# item_2022_BlockDiagram_01.net
KiCad netlist of a schematic drawn in EAGLE
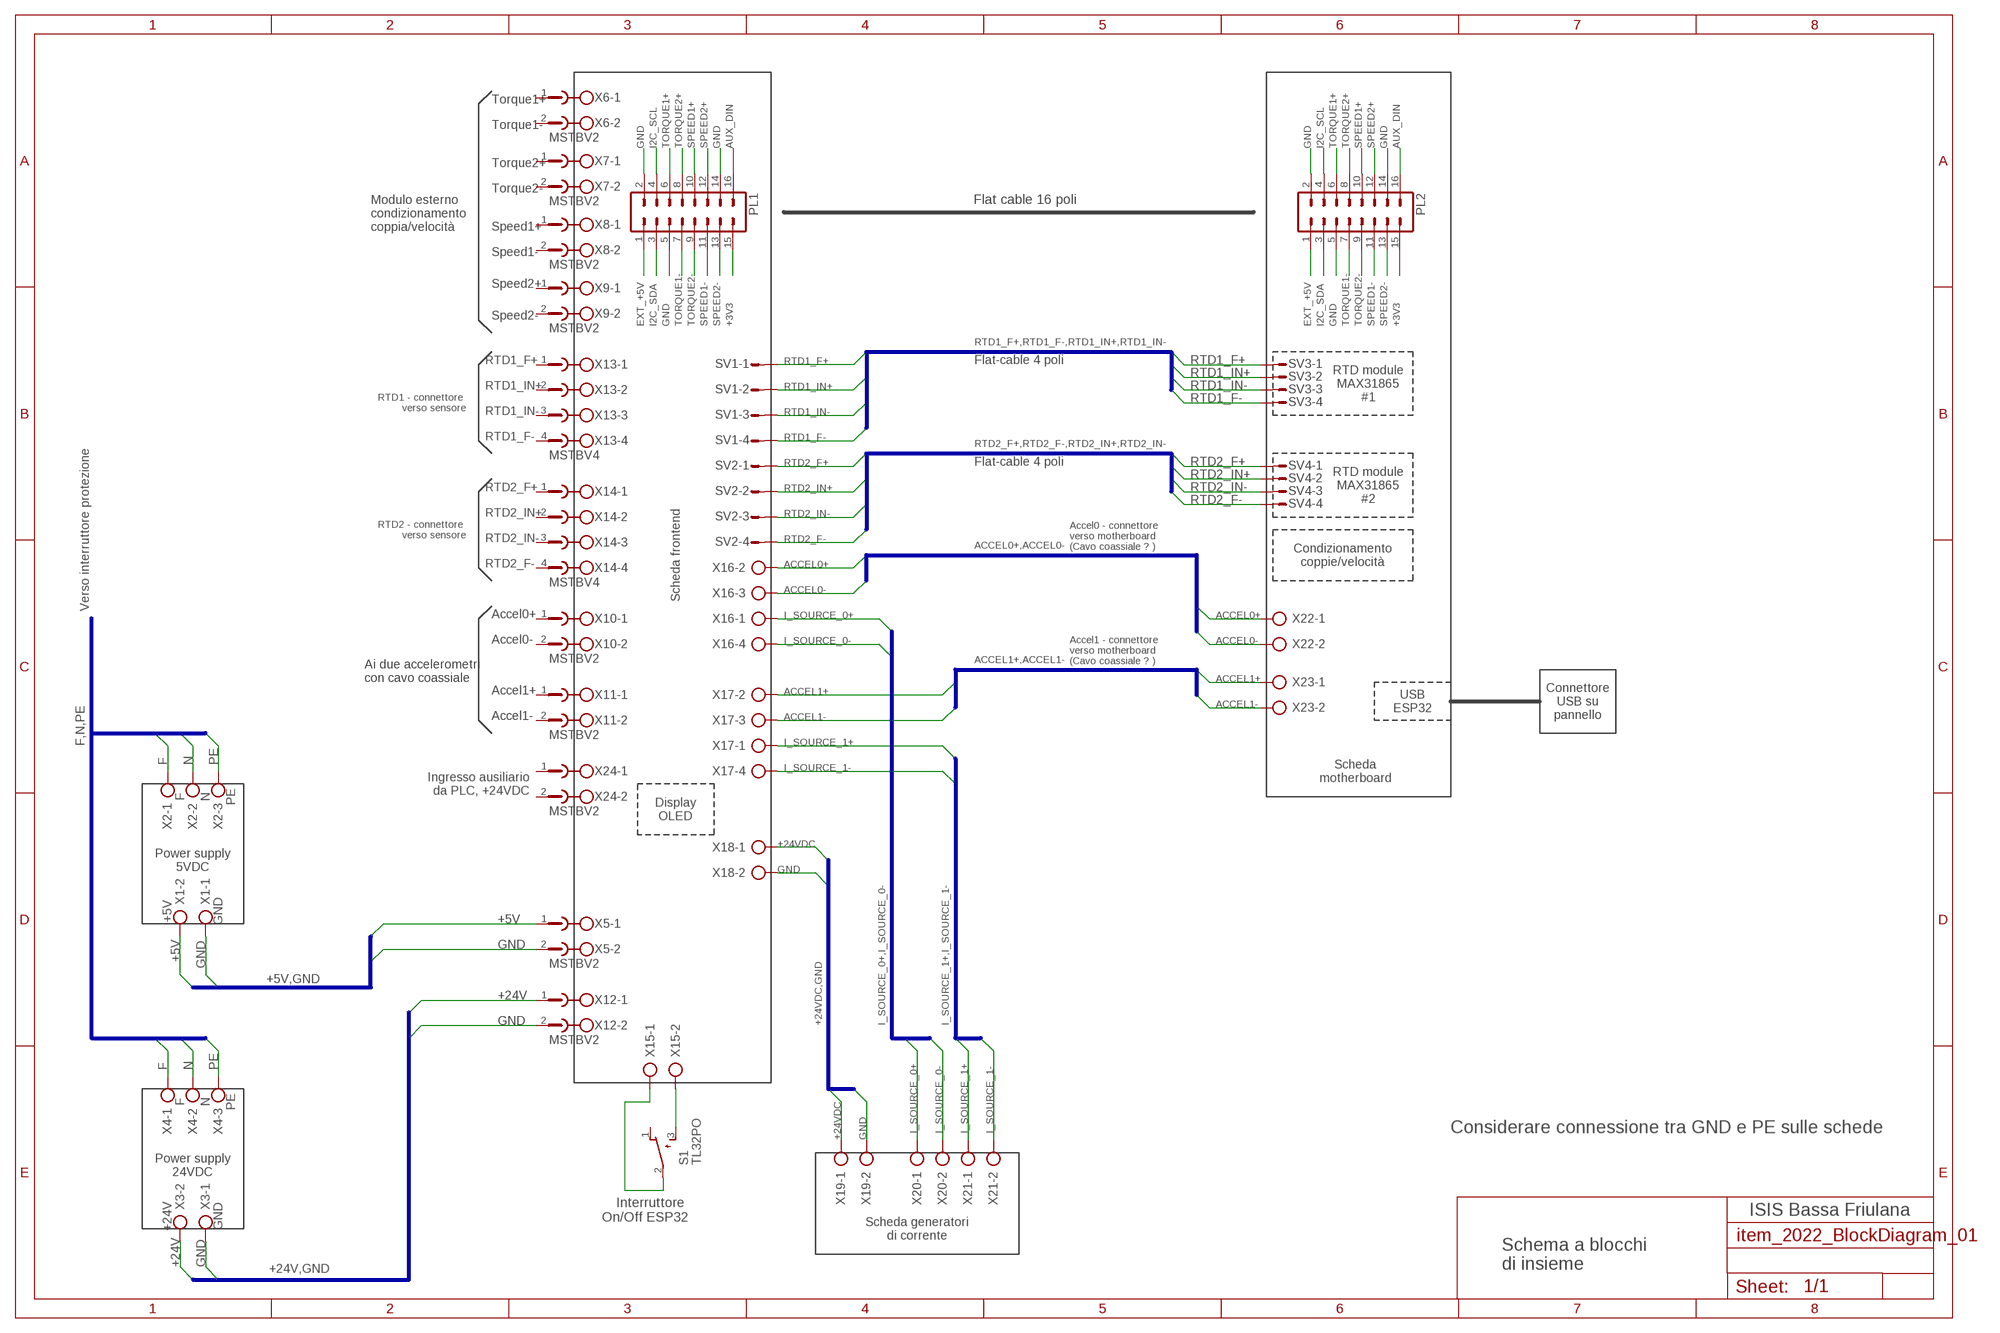
[diagram p0: schematic, sheet 1]

(export (version "E")
  (design (tool "Eeschema 10.0.6"))
  (components
    (comp (ref "PL1")
      (value "16V")
      (footprint "eagle-import:16V")
      (libsource (lib "eagle-import") (part "16V"))
    )
    (comp (ref "PL2")
      (value "16V")
      (footprint "eagle-import:16V")
      (libsource (lib "eagle-import") (part "16V"))
    )
    (comp (ref "S1")
      (value "TL32PO")
      (footprint "eagle-import:TL3XPO")
      (libsource (lib "eagle-import") (part "TL32PO"))
    )
    (comp (ref "SV1")
      (value "S04P")
      (footprint "eagle-import:S04P")
      (libsource (lib "eagle-import") (part "S04P"))
    )
    (comp (ref "SV2")
      (value "S04P")
      (footprint "eagle-import:S04P")
      (libsource (lib "eagle-import") (part "S04P"))
    )
    (comp (ref "SV3")
      (value "S04P")
      (footprint "eagle-import:S04P")
      (libsource (lib "eagle-import") (part "S04P"))
    )
    (comp (ref "SV4")
      (value "S04P")
      (footprint "eagle-import:S04P")
      (libsource (lib "eagle-import") (part "S04P"))
    )
    (comp (ref "X1")
      (value "+5V")
      (footprint "eagle-import:AK500_2")
      (libsource (lib "eagle-import") (part "AK500/2"))
    )
    (comp (ref "X2")
      (value "AK500/3")
      (footprint "eagle-import:AK500_3")
      (libsource (lib "eagle-import") (part "AK500/3"))
    )
    (comp (ref "X3")
      (value "+5V")
      (footprint "eagle-import:AK500_2")
      (libsource (lib "eagle-import") (part "AK500/2"))
    )
    (comp (ref "X4")
      (value "AK500/3")
      (footprint "eagle-import:AK500_3")
      (libsource (lib "eagle-import") (part "AK500/3"))
    )
    (comp (ref "X5")
      (value "MSTBV2")
      (footprint "eagle-import:MSTBV2")
      (fields (field (name "MPN") "MSTBV 2,5/2-GF-5.08"))
      (libsource (lib "eagle-import") (part "MSTBV2"))
    )
    (comp (ref "X6")
      (value "MSTBV2")
      (footprint "eagle-import:MSTBV2")
      (fields (field (name "MPN") "MSTBV 2,5/2-GF-5.08"))
      (libsource (lib "eagle-import") (part "MSTBV2"))
    )
    (comp (ref "X7")
      (value "MSTBV2")
      (footprint "eagle-import:MSTBV2")
      (fields (field (name "MPN") "MSTBV 2,5/2-GF-5.08"))
      (libsource (lib "eagle-import") (part "MSTBV2"))
    )
    (comp (ref "X8")
      (value "MSTBV2")
      (footprint "eagle-import:MSTBV2")
      (fields (field (name "MPN") "MSTBV 2,5/2-GF-5.08"))
      (libsource (lib "eagle-import") (part "MSTBV2"))
    )
    (comp (ref "X9")
      (value "MSTBV2")
      (footprint "eagle-import:MSTBV2")
      (fields (field (name "MPN") "MSTBV 2,5/2-GF-5.08"))
      (libsource (lib "eagle-import") (part "MSTBV2"))
    )
    (comp (ref "X10")
      (value "MSTBV2")
      (footprint "eagle-import:MSTBV2")
      (fields (field (name "MPN") "MSTBV 2,5/2-GF-5.08"))
      (libsource (lib "eagle-import") (part "MSTBV2"))
    )
    (comp (ref "X11")
      (value "MSTBV2")
      (footprint "eagle-import:MSTBV2")
      (fields (field (name "MPN") "MSTBV 2,5/2-GF-5.08"))
      (libsource (lib "eagle-import") (part "MSTBV2"))
    )
    (comp (ref "X12")
      (value "MSTBV2")
      (footprint "eagle-import:MSTBV2")
      (fields (field (name "MPN") "MSTBV 2,5/2-GF-5.08"))
      (libsource (lib "eagle-import") (part "MSTBV2"))
    )
    (comp (ref "X13")
      (value "MSTBV4")
      (footprint "eagle-import:MSTBV4")
      (fields (field (name "MPN") "MSTBV 2,5/4-GF-5.08"))
      (libsource (lib "eagle-import") (part "MSTBV4"))
    )
    (comp (ref "X14")
      (value "MSTBV4")
      (footprint "eagle-import:MSTBV4")
      (fields (field (name "MPN") "MSTBV 2,5/4-GF-5.08"))
      (libsource (lib "eagle-import") (part "MSTBV4"))
    )
    (comp (ref "X15")
      (value "AK500/2")
      (footprint "eagle-import:AK500_2")
      (libsource (lib "eagle-import") (part "AK500/2"))
    )
    (comp (ref "X16")
      (value "AK500/4")
      (footprint "eagle-import:AK500_4")
      (libsource (lib "eagle-import") (part "AK500/4"))
    )
    (comp (ref "X17")
      (value "AK500/4")
      (footprint "eagle-import:AK500_4")
      (libsource (lib "eagle-import") (part "AK500/4"))
    )
    (comp (ref "X18")
      (value "AK500/2")
      (footprint "eagle-import:AK500_2")
      (libsource (lib "eagle-import") (part "AK500/2"))
    )
    (comp (ref "X19")
      (value "AK500/2")
      (footprint "eagle-import:AK500_2")
      (libsource (lib "eagle-import") (part "AK500/2"))
    )
    (comp (ref "X20")
      (value "AK500/2")
      (footprint "eagle-import:AK500_2")
      (libsource (lib "eagle-import") (part "AK500/2"))
    )
    (comp (ref "X21")
      (value "AK500/2")
      (footprint "eagle-import:AK500_2")
      (libsource (lib "eagle-import") (part "AK500/2"))
    )
    (comp (ref "X22")
      (value "AK500/2")
      (footprint "eagle-import:AK500_2")
      (libsource (lib "eagle-import") (part "AK500/2"))
    )
    (comp (ref "X23")
      (value "AK500/2")
      (footprint "eagle-import:AK500_2")
      (libsource (lib "eagle-import") (part "AK500/2"))
    )
    (comp (ref "X24")
      (value "MSTBV2")
      (footprint "eagle-import:MSTBV2")
      (fields (field (name "MPN") "MSTBV 2,5/2-GF-5.08"))
      (libsource (lib "eagle-import") (part "MSTBV2"))
    )
  )
  (nets
    (net (code "1") (name "/+3V3") (class "Default")
      (node (ref "PL1") (pin "15") (pinfunction "15_15") (pintype "passive"))
      (node (ref "PL2") (pin "15") (pinfunction "15_15") (pintype "passive"))
    )
    (net (code "2") (name "/+5V") (class "Default")
      (node (ref "X1") (pin "2") (pinfunction "KL_2") (pintype "passive"))
      (node (ref "X5") (pin "1") (pinfunction "1_1") (pintype "passive"))
    )
    (net (code "3") (name "/+24V") (class "Default")
      (node (ref "X12") (pin "1") (pinfunction "1_1") (pintype "passive"))
      (node (ref "X3") (pin "2") (pinfunction "KL_2") (pintype "passive"))
    )
    (net (code "4") (name "/+24VDC") (class "Default")
      (node (ref "X18") (pin "1") (pinfunction "KL_1") (pintype "passive"))
      (node (ref "X19") (pin "1") (pinfunction "KL_1") (pintype "passive"))
    )
    (net (code "5") (name "/ACCEL0+") (class "Default")
      (node (ref "X16") (pin "2") (pinfunction "KL_2") (pintype "passive"))
      (node (ref "X22") (pin "1") (pinfunction "KL_1") (pintype "passive"))
    )
    (net (code "6") (name "/ACCEL0-") (class "Default")
      (node (ref "X16") (pin "3") (pinfunction "KL_3") (pintype "passive"))
      (node (ref "X22") (pin "2") (pinfunction "KL_2") (pintype "passive"))
    )
    (net (code "7") (name "/ACCEL1+") (class "Default")
      (node (ref "X17") (pin "2") (pinfunction "KL_2") (pintype "passive"))
      (node (ref "X23") (pin "1") (pinfunction "KL_1") (pintype "passive"))
    )
    (net (code "8") (name "/ACCEL1-") (class "Default")
      (node (ref "X17") (pin "3") (pinfunction "KL_3") (pintype "passive"))
      (node (ref "X23") (pin "2") (pinfunction "KL_2") (pintype "passive"))
    )
    (net (code "9") (name "/AUX_DIN") (class "Default")
      (node (ref "PL1") (pin "16") (pinfunction "16_16") (pintype "passive"))
      (node (ref "PL2") (pin "16") (pinfunction "16_16") (pintype "passive"))
    )
    (net (code "10") (name "/EXT_+5V") (class "Default")
      (node (ref "PL1") (pin "1") (pinfunction "1_1") (pintype "passive"))
      (node (ref "PL2") (pin "1") (pinfunction "1_1") (pintype "passive"))
    )
    (net (code "11") (name "/F") (class "Default")
      (node (ref "X2") (pin "1") (pinfunction "KL_1") (pintype "passive"))
      (node (ref "X4") (pin "1") (pinfunction "KL_1") (pintype "passive"))
    )
    (net (code "12") (name "/GND") (class "Default")
      (node (ref "PL1") (pin "14") (pinfunction "14_14") (pintype "passive"))
      (node (ref "PL1") (pin "2") (pinfunction "2_2") (pintype "passive"))
      (node (ref "PL1") (pin "5") (pinfunction "5_5") (pintype "passive"))
      (node (ref "PL2") (pin "14") (pinfunction "14_14") (pintype "passive"))
      (node (ref "PL2") (pin "2") (pinfunction "2_2") (pintype "passive"))
      (node (ref "PL2") (pin "5") (pinfunction "5_5") (pintype "passive"))
      (node (ref "X1") (pin "1") (pinfunction "KL_1") (pintype "passive"))
      (node (ref "X12") (pin "2") (pinfunction "1_2") (pintype "passive"))
      (node (ref "X18") (pin "2") (pinfunction "KL_2") (pintype "passive"))
      (node (ref "X19") (pin "2") (pinfunction "KL_2") (pintype "passive"))
      (node (ref "X3") (pin "1") (pinfunction "KL_1") (pintype "passive"))
      (node (ref "X5") (pin "2") (pinfunction "1_2") (pintype "passive"))
    )
    (net (code "13") (name "/I2C_SCL") (class "Default")
      (node (ref "PL1") (pin "4") (pinfunction "4_4") (pintype "passive"))
      (node (ref "PL2") (pin "4") (pinfunction "4_4") (pintype "passive"))
    )
    (net (code "14") (name "/I2C_SDA") (class "Default")
      (node (ref "PL1") (pin "3") (pinfunction "3_3") (pintype "passive"))
      (node (ref "PL2") (pin "3") (pinfunction "3_3") (pintype "passive"))
    )
    (net (code "15") (name "/I_SOURCE_0+") (class "Default")
      (node (ref "X16") (pin "1") (pinfunction "KL_1") (pintype "passive"))
      (node (ref "X20") (pin "1") (pinfunction "KL_1") (pintype "passive"))
    )
    (net (code "16") (name "/I_SOURCE_0-") (class "Default")
      (node (ref "X16") (pin "4") (pinfunction "KL_4") (pintype "passive"))
      (node (ref "X20") (pin "2") (pinfunction "KL_2") (pintype "passive"))
    )
    (net (code "17") (name "/I_SOURCE_1+") (class "Default")
      (node (ref "X17") (pin "1") (pinfunction "KL_1") (pintype "passive"))
      (node (ref "X21") (pin "1") (pinfunction "KL_1") (pintype "passive"))
    )
    (net (code "18") (name "/I_SOURCE_1-") (class "Default")
      (node (ref "X17") (pin "4") (pinfunction "KL_4") (pintype "passive"))
      (node (ref "X21") (pin "2") (pinfunction "KL_2") (pintype "passive"))
    )
    (net (code "19") (name "/N") (class "Default")
      (node (ref "X2") (pin "2") (pinfunction "KL_2") (pintype "passive"))
      (node (ref "X4") (pin "2") (pinfunction "KL_2") (pintype "passive"))
    )
    (net (code "20") (name "/PE") (class "Default")
      (node (ref "X2") (pin "3") (pinfunction "KL_3") (pintype "passive"))
      (node (ref "X4") (pin "3") (pinfunction "KL_3") (pintype "passive"))
    )
    (net (code "21") (name "/RTD1_F+") (class "Default")
      (node (ref "SV1") (pin "1") (pinfunction "S_1") (pintype "passive"))
      (node (ref "SV3") (pin "1") (pinfunction "S_1") (pintype "passive"))
    )
    (net (code "22") (name "/RTD1_F-") (class "Default")
      (node (ref "SV1") (pin "4") (pinfunction "S_4") (pintype "passive"))
      (node (ref "SV3") (pin "4") (pinfunction "S_4") (pintype "passive"))
    )
    (net (code "23") (name "/RTD1_IN+") (class "Default")
      (node (ref "SV1") (pin "2") (pinfunction "S_2") (pintype "passive"))
      (node (ref "SV3") (pin "2") (pinfunction "S_2") (pintype "passive"))
    )
    (net (code "24") (name "/RTD1_IN-") (class "Default")
      (node (ref "SV1") (pin "3") (pinfunction "S_3") (pintype "passive"))
      (node (ref "SV3") (pin "3") (pinfunction "S_3") (pintype "passive"))
    )
    (net (code "25") (name "/RTD2_F+") (class "Default")
      (node (ref "SV2") (pin "1") (pinfunction "S_1") (pintype "passive"))
      (node (ref "SV4") (pin "1") (pinfunction "S_1") (pintype "passive"))
    )
    (net (code "26") (name "/RTD2_F-") (class "Default")
      (node (ref "SV2") (pin "4") (pinfunction "S_4") (pintype "passive"))
      (node (ref "SV4") (pin "4") (pinfunction "S_4") (pintype "passive"))
    )
    (net (code "27") (name "/RTD2_IN+") (class "Default")
      (node (ref "SV2") (pin "2") (pinfunction "S_2") (pintype "passive"))
      (node (ref "SV4") (pin "2") (pinfunction "S_2") (pintype "passive"))
    )
    (net (code "28") (name "/RTD2_IN-") (class "Default")
      (node (ref "SV2") (pin "3") (pinfunction "S_3") (pintype "passive"))
      (node (ref "SV4") (pin "3") (pinfunction "S_3") (pintype "passive"))
    )
    (net (code "29") (name "/SPEED1+") (class "Default")
      (node (ref "PL1") (pin "10") (pinfunction "10_10") (pintype "passive"))
      (node (ref "PL2") (pin "10") (pinfunction "10_10") (pintype "passive"))
    )
    (net (code "30") (name "/SPEED1-") (class "Default")
      (node (ref "PL1") (pin "11") (pinfunction "11_11") (pintype "passive"))
      (node (ref "PL2") (pin "11") (pinfunction "11_11") (pintype "passive"))
    )
    (net (code "31") (name "/SPEED2+") (class "Default")
      (node (ref "PL1") (pin "12") (pinfunction "12_12") (pintype "passive"))
      (node (ref "PL2") (pin "12") (pinfunction "12_12") (pintype "passive"))
    )
    (net (code "32") (name "/SPEED2-") (class "Default")
      (node (ref "PL1") (pin "13") (pinfunction "13_13") (pintype "passive"))
      (node (ref "PL2") (pin "13") (pinfunction "13_13") (pintype "passive"))
    )
    (net (code "33") (name "/TORQUE1+") (class "Default")
      (node (ref "PL1") (pin "6") (pinfunction "6_6") (pintype "passive"))
      (node (ref "PL2") (pin "6") (pinfunction "6_6") (pintype "passive"))
    )
    (net (code "34") (name "/TORQUE1-") (class "Default")
      (node (ref "PL1") (pin "7") (pinfunction "7_7") (pintype "passive"))
      (node (ref "PL2") (pin "7") (pinfunction "7_7") (pintype "passive"))
    )
    (net (code "35") (name "/TORQUE2+") (class "Default")
      (node (ref "PL1") (pin "8") (pinfunction "8_8") (pintype "passive"))
      (node (ref "PL2") (pin "8") (pinfunction "8_8") (pintype "passive"))
    )
    (net (code "36") (name "/TORQUE2-") (class "Default")
      (node (ref "PL1") (pin "9") (pinfunction "9_9") (pintype "passive"))
      (node (ref "PL2") (pin "9") (pinfunction "9_9") (pintype "passive"))
    )
    (net (code "47") (name "Net-(S1-P)") (class "Default")
      (node (ref "S1") (pin "2") (pinfunction "P_2") (pintype "passive"))
      (node (ref "X15") (pin "1") (pinfunction "KL_1") (pintype "passive"))
    )
    (net (code "48") (name "Net-(S1-S)") (class "Default")
      (node (ref "S1") (pin "3") (pinfunction "S_3") (pintype "passive"))
      (node (ref "X15") (pin "2") (pinfunction "KL_2") (pintype "passive"))
    )
    (net (code "49") (name "unconnected-(S1-O-Pad1)") (class "Default")
      (node (ref "S1") (pin "1") (pinfunction "O_1") (pintype "passive"))
    )
    (net (code "50") (name "unconnected-(X6-Pad1)") (class "Default")
      (node (ref "X6") (pin "1") (pinfunction "1_1") (pintype "passive"))
    )
    (net (code "51") (name "unconnected-(X6B-1-Pad2)") (class "Default")
      (node (ref "X6") (pin "2") (pinfunction "1_2") (pintype "passive"))
    )
    (net (code "52") (name "unconnected-(X7-Pad1)") (class "Default")
      (node (ref "X7") (pin "1") (pinfunction "1_1") (pintype "passive"))
    )
    (net (code "53") (name "unconnected-(X7B-1-Pad2)") (class "Default")
      (node (ref "X7") (pin "2") (pinfunction "1_2") (pintype "passive"))
    )
    (net (code "54") (name "unconnected-(X8-Pad1)") (class "Default")
      (node (ref "X8") (pin "1") (pinfunction "1_1") (pintype "passive"))
    )
    (net (code "55") (name "unconnected-(X8B-1-Pad2)") (class "Default")
      (node (ref "X8") (pin "2") (pinfunction "1_2") (pintype "passive"))
    )
    (net (code "56") (name "unconnected-(X9-Pad1)") (class "Default")
      (node (ref "X9") (pin "1") (pinfunction "1_1") (pintype "passive"))
    )
    (net (code "57") (name "unconnected-(X9B-1-Pad2)") (class "Default")
      (node (ref "X9") (pin "2") (pinfunction "1_2") (pintype "passive"))
    )
    (net (code "58") (name "unconnected-(X10-Pad1)") (class "Default")
      (node (ref "X10") (pin "1") (pinfunction "1_1") (pintype "passive"))
    )
    (net (code "59") (name "unconnected-(X10B-1-Pad2)") (class "Default")
      (node (ref "X10") (pin "2") (pinfunction "1_2") (pintype "passive"))
    )
    (net (code "60") (name "unconnected-(X11-Pad1)") (class "Default")
      (node (ref "X11") (pin "1") (pinfunction "1_1") (pintype "passive"))
    )
    (net (code "61") (name "unconnected-(X11B-1-Pad2)") (class "Default")
      (node (ref "X11") (pin "2") (pinfunction "1_2") (pintype "passive"))
    )
    (net (code "62") (name "unconnected-(X13-Pad1)") (class "Default")
      (node (ref "X13") (pin "1") (pinfunction "1_1") (pintype "passive"))
    )
    (net (code "63") (name "unconnected-(X13B-1-Pad2)") (class "Default")
      (node (ref "X13") (pin "2") (pinfunction "1_2") (pintype "passive"))
    )
    (net (code "64") (name "unconnected-(X13C-1-Pad3)") (class "Default")
      (node (ref "X13") (pin "3") (pinfunction "1_3") (pintype "passive"))
    )
    (net (code "65") (name "unconnected-(X13D-1-Pad4)") (class "Default")
      (node (ref "X13") (pin "4") (pinfunction "1_4") (pintype "passive"))
    )
    (net (code "66") (name "unconnected-(X14-Pad1)") (class "Default")
      (node (ref "X14") (pin "1") (pinfunction "1_1") (pintype "passive"))
    )
    (net (code "67") (name "unconnected-(X14B-1-Pad2)") (class "Default")
      (node (ref "X14") (pin "2") (pinfunction "1_2") (pintype "passive"))
    )
    (net (code "68") (name "unconnected-(X14C-1-Pad3)") (class "Default")
      (node (ref "X14") (pin "3") (pinfunction "1_3") (pintype "passive"))
    )
    (net (code "69") (name "unconnected-(X14D-1-Pad4)") (class "Default")
      (node (ref "X14") (pin "4") (pinfunction "1_4") (pintype "passive"))
    )
    (net (code "70") (name "unconnected-(X24-Pad1)") (class "Default")
      (node (ref "X24") (pin "1") (pinfunction "1_1") (pintype "passive"))
    )
    (net (code "71") (name "unconnected-(X24B-1-Pad2)") (class "Default")
      (node (ref "X24") (pin "2") (pinfunction "1_2") (pintype "passive"))
    )
  )
)
